# doorbell.net
KiCad netlist of a schematic drawn in EAGLE
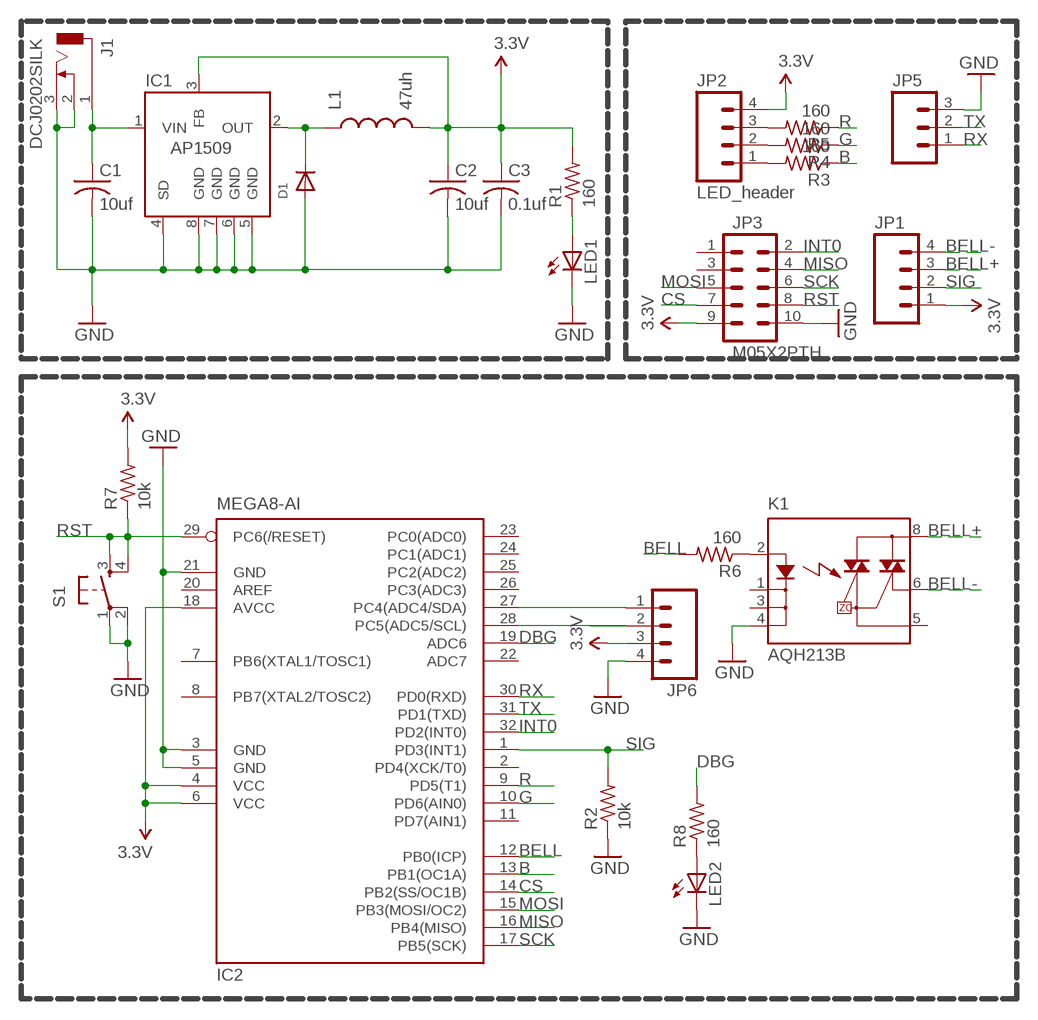
[diagram p0: schematic, sheet 1]

(export (version "E")
  (design (tool "Eeschema 10.0.6"))
  (components
    (comp (ref "C1")
      (value "10uf")
      (footprint "eagle-import:C1206")
      (libsource (lib "eagle-import") (part "C-USC1206"))
    )
    (comp (ref "C2")
      (value "10uf")
      (footprint "eagle-import:C1206")
      (libsource (lib "eagle-import") (part "C-USC1206"))
    )
    (comp (ref "C3")
      (value "0.1uf")
      (footprint "eagle-import:C1206")
      (libsource (lib "eagle-import") (part "C-USC1206"))
    )
    (comp (ref "D1")
      (value "DIODESOD-123")
      (footprint "eagle-import:SOD-123")
      (libsource (lib "eagle-import") (part "DIODESOD-123"))
    )
    (comp (ref "IC1")
      (value "AP1509")
      (footprint "eagle-import:SOP-8")
      (libsource (lib "eagle-import") (part "AP1509"))
    )
    (comp (ref "IC2")
      (value "MEGA8-AI")
      (footprint "eagle-import:TQFP32-08")
      (fields (field (name "MPN") "ATMEGA8-16AU"))
      (libsource (lib "eagle-import") (part "MEGA8-AI"))
    )
    (comp (ref "J1")
      (value "DCJ0202SILK")
      (footprint "eagle-import:DCJ0202_SILK")
      (libsource (lib "eagle-import") (part "DCJ0202SILK"))
    )
    (comp (ref "JP1")
      (value "M04SCREW_SILK")
      (footprint "eagle-import:SCREWTERMINAL-3.5MM-4_SILK")
      (libsource (lib "eagle-import") (part "M04SCREW_SILK"))
    )
    (comp (ref "JP2")
      (value "LED_header")
      (footprint "eagle-import:1X04")
      (libsource (lib "eagle-import") (part "M04PTH"))
    )
    (comp (ref "JP3")
      (value "M05X2PTH")
      (footprint "eagle-import:AVR_ICSP")
      (libsource (lib "eagle-import") (part "M05X2PTH"))
    )
    (comp (ref "JP5")
      (value "M03PTH")
      (footprint "eagle-import:1X03")
      (libsource (lib "eagle-import") (part "M03PTH"))
    )
    (comp (ref "JP6")
      (value "M04PTH")
      (footprint "eagle-import:1X04")
      (libsource (lib "eagle-import") (part "M04PTH"))
    )
    (comp (ref "K1")
      (value "AQH213B")
      (footprint "eagle-import:DIL08SMD")
      (libsource (lib "eagle-import") (part "AQH213B"))
    )
    (comp (ref "L1")
      (value "47uh")
      (footprint "eagle-import:1210")
      (libsource (lib "eagle-import") (part "INDUCTOR1210"))
    )
    (comp (ref "LED1")
      (value "LEDSMT1206")
      (footprint "eagle-import:1206")
      (libsource (lib "eagle-import") (part "LEDSMT1206"))
    )
    (comp (ref "LED2")
      (value "LEDSMT1206")
      (footprint "eagle-import:1206")
      (libsource (lib "eagle-import") (part "LEDSMT1206"))
    )
    (comp (ref "R1")
      (value "160")
      (footprint "eagle-import:R1206")
      (libsource (lib "eagle-import") (part "R-US_R1206"))
    )
    (comp (ref "R2")
      (value "10k")
      (footprint "eagle-import:R1206")
      (libsource (lib "eagle-import") (part "R-US_R1206"))
    )
    (comp (ref "R3")
      (value "160")
      (footprint "eagle-import:R1206")
      (libsource (lib "eagle-import") (part "R-US_R1206"))
    )
    (comp (ref "R4")
      (value "160")
      (footprint "eagle-import:R1206")
      (libsource (lib "eagle-import") (part "R-US_R1206"))
    )
    (comp (ref "R5")
      (value "160")
      (footprint "eagle-import:R1206")
      (libsource (lib "eagle-import") (part "R-US_R1206"))
    )
    (comp (ref "R6")
      (value "160")
      (footprint "eagle-import:R1206")
      (libsource (lib "eagle-import") (part "R-US_R1206"))
    )
    (comp (ref "R7")
      (value "10k")
      (footprint "eagle-import:R1206")
      (libsource (lib "eagle-import") (part "R-US_R1206"))
    )
    (comp (ref "R8")
      (value "160")
      (footprint "eagle-import:R1206")
      (libsource (lib "eagle-import") (part "R-US_R1206"))
    )
    (comp (ref "S1")
      (value "TAC_SWITCHSMD")
      (footprint "eagle-import:TACTILE_SWITCH_SMD")
      (libsource (lib "eagle-import") (part "TAC_SWITCHSMD"))
    )
  )
  (nets
    (net (code "1") (name "/B") (class "Default")
      (node (ref "IC2") (pin "13") (pinfunction "PB1(OC1A)_13") (pintype "bidirectional"))
      (node (ref "R3") (pin "1") (pinfunction "1_1") (pintype "passive"))
    )
    (net (code "2") (name "/BELL") (class "Default")
      (node (ref "IC2") (pin "12") (pinfunction "PB0(ICP)_12") (pintype "bidirectional"))
      (node (ref "R6") (pin "2") (pinfunction "2_2") (pintype "passive"))
    )
    (net (code "3") (name "/BELL+") (class "Default")
      (node (ref "JP1") (pin "3") (pinfunction "3_3") (pintype "passive"))
      (node (ref "K1") (pin "8") (pinfunction "DS1_8") (pintype "passive"))
    )
    (net (code "4") (name "/BELL-") (class "Default")
      (node (ref "JP1") (pin "4") (pinfunction "4_4") (pintype "passive"))
      (node (ref "K1") (pin "6") (pinfunction "DS3_6") (pintype "passive"))
    )
    (net (code "5") (name "/CS") (class "Default")
      (node (ref "IC2") (pin "14") (pinfunction "PB2(SS/OC1B)_14") (pintype "bidirectional"))
      (node (ref "JP3") (pin "7") (pinfunction "7_7") (pintype "passive"))
    )
    (net (code "6") (name "/DBG") (class "Default")
      (node (ref "IC2") (pin "19") (pinfunction "ADC6_19") (pintype "bidirectional"))
      (node (ref "R8") (pin "2") (pinfunction "2_2") (pintype "passive"))
    )
    (net (code "7") (name "/G") (class "Default")
      (node (ref "IC2") (pin "10") (pinfunction "PD6(AIN0)_10") (pintype "bidirectional"))
      (node (ref "R4") (pin "1") (pinfunction "1_1") (pintype "passive"))
    )
    (net (code "8") (name "/INT0") (class "Default")
      (node (ref "IC2") (pin "32") (pinfunction "PD2(INT0)_32") (pintype "bidirectional"))
      (node (ref "JP3") (pin "2") (pinfunction "2_2") (pintype "passive"))
    )
    (net (code "9") (name "/MISO") (class "Default")
      (node (ref "IC2") (pin "16") (pinfunction "PB4(MISO)_16") (pintype "bidirectional"))
      (node (ref "JP3") (pin "4") (pinfunction "4_4") (pintype "passive"))
    )
    (net (code "10") (name "/MOSI") (class "Default")
      (node (ref "IC2") (pin "15") (pinfunction "PB3(MOSI/OC2)_15") (pintype "bidirectional"))
      (node (ref "JP3") (pin "5") (pinfunction "5_5") (pintype "passive"))
    )
    (net (code "11") (name "/R") (class "Default")
      (node (ref "IC2") (pin "9") (pinfunction "PD5(T1)_9") (pintype "bidirectional"))
      (node (ref "R5") (pin "1") (pinfunction "1_1") (pintype "passive"))
    )
    (net (code "12") (name "/RST") (class "Default")
      (node (ref "IC2") (pin "29") (pinfunction "PC6(/RESET)_29") (pintype "bidirectional"))
      (node (ref "JP3") (pin "8") (pinfunction "8_8") (pintype "passive"))
      (node (ref "R7") (pin "1") (pinfunction "1_1") (pintype "passive"))
      (node (ref "S1") (pin "3") (pinfunction "3_3") (pintype "passive"))
      (node (ref "S1") (pin "4") (pinfunction "4_4") (pintype "passive"))
    )
    (net (code "13") (name "/RX") (class "Default")
      (node (ref "IC2") (pin "30") (pinfunction "PD0(RXD)_30") (pintype "bidirectional"))
      (node (ref "JP5") (pin "1") (pinfunction "1_1") (pintype "passive"))
    )
    (net (code "14") (name "/SCK") (class "Default")
      (node (ref "IC2") (pin "17") (pinfunction "PB5(SCK)_17") (pintype "bidirectional"))
      (node (ref "JP3") (pin "6") (pinfunction "6_6") (pintype "passive"))
    )
    (net (code "15") (name "/SIG") (class "Default")
      (node (ref "IC2") (pin "1") (pinfunction "PD3(INT1)_1") (pintype "bidirectional"))
      (node (ref "JP1") (pin "2") (pinfunction "2_2") (pintype "passive"))
      (node (ref "R2") (pin "2") (pinfunction "2_2") (pintype "passive"))
    )
    (net (code "16") (name "/TX") (class "Default")
      (node (ref "IC2") (pin "31") (pinfunction "PD1(TXD)_31") (pintype "bidirectional"))
      (node (ref "JP5") (pin "2") (pinfunction "2_2") (pintype "passive"))
    )
    (net (code "17") (name "3.3V") (class "Default")
      (node (ref "C2") (pin "1") (pinfunction "1_1") (pintype "passive"))
      (node (ref "C3") (pin "1") (pinfunction "1_1") (pintype "passive"))
      (node (ref "IC1") (pin "3") (pinfunction "FB_3") (pintype "bidirectional"))
      (node (ref "IC2") (pin "18") (pinfunction "AVCC_18") (pintype "power_in"))
      (node (ref "IC2") (pin "4") (pinfunction "VCC_4") (pintype "power_in"))
      (node (ref "IC2") (pin "6") (pinfunction "VCC_6") (pintype "power_in"))
      (node (ref "JP1") (pin "1") (pinfunction "1_1") (pintype "passive"))
      (node (ref "JP2") (pin "4") (pinfunction "4_4") (pintype "passive"))
      (node (ref "JP3") (pin "9") (pinfunction "9_9") (pintype "passive"))
      (node (ref "JP6") (pin "3") (pinfunction "3_3") (pintype "passive"))
      (node (ref "L1") (pin "2") (pinfunction "2_2") (pintype "passive"))
      (node (ref "R1") (pin "2") (pinfunction "2_2") (pintype "passive"))
      (node (ref "R7") (pin "2") (pinfunction "2_2") (pintype "passive"))
    )
    (net (code "18") (name "GND") (class "Default")
      (node (ref "C1") (pin "2") (pinfunction "2_2") (pintype "passive"))
      (node (ref "C2") (pin "2") (pinfunction "2_2") (pintype "passive"))
      (node (ref "C3") (pin "2") (pinfunction "2_2") (pintype "passive"))
      (node (ref "D1") (pin "A") (pinfunction "A_A") (pintype "passive"))
      (node (ref "IC1") (pin "4") (pinfunction "SD_4") (pintype "bidirectional"))
      (node (ref "IC1") (pin "5") (pinfunction "GND_5") (pintype "bidirectional"))
      (node (ref "IC1") (pin "6") (pinfunction "GND_6") (pintype "bidirectional"))
      (node (ref "IC1") (pin "7") (pinfunction "GND_7") (pintype "bidirectional"))
      (node (ref "IC1") (pin "8") (pinfunction "GND_8") (pintype "bidirectional"))
      (node (ref "IC2") (pin "21") (pinfunction "GND_21") (pintype "power_in"))
      (node (ref "IC2") (pin "3") (pinfunction "GND_3") (pintype "power_in"))
      (node (ref "IC2") (pin "5") (pinfunction "GND_5") (pintype "power_in"))
      (node (ref "J1") (pin "2") (pinfunction "2_2") (pintype "passive"))
      (node (ref "J1") (pin "3") (pinfunction "3_3") (pintype "passive"))
      (node (ref "JP3") (pin "10") (pinfunction "10_10") (pintype "passive"))
      (node (ref "JP5") (pin "3") (pinfunction "3_3") (pintype "passive"))
      (node (ref "JP6") (pin "4") (pinfunction "4_4") (pintype "passive"))
      (node (ref "K1") (pin "4") (pinfunction "K2_4") (pintype "passive"))
      (node (ref "LED1") (pin "C") (pinfunction "C_C") (pintype "passive"))
      (node (ref "LED2") (pin "C") (pinfunction "C_C") (pintype "passive"))
      (node (ref "R2") (pin "1") (pinfunction "1_1") (pintype "passive"))
      (node (ref "S1") (pin "1") (pinfunction "1_1") (pintype "passive"))
      (node (ref "S1") (pin "2") (pinfunction "2_2") (pintype "passive"))
    )
    (net (code "19") (name "Net-(IC1-OUT)") (class "Default")
      (node (ref "D1") (pin "C") (pinfunction "C_C") (pintype "passive"))
      (node (ref "IC1") (pin "2") (pinfunction "OUT_2") (pintype "bidirectional"))
      (node (ref "L1") (pin "1") (pinfunction "1_1") (pintype "passive"))
    )
    (net (code "20") (name "Net-(IC1-VIN)") (class "Default")
      (node (ref "C1") (pin "1") (pinfunction "1_1") (pintype "passive"))
      (node (ref "IC1") (pin "1") (pinfunction "VIN_1") (pintype "bidirectional"))
      (node (ref "J1") (pin "1") (pinfunction "1_1") (pintype "passive"))
    )
    (net (code "21") (name "Net-(IC2-PC4(ADC4{slash}SDA))") (class "Default")
      (node (ref "IC2") (pin "27") (pinfunction "PC4(ADC4/SDA)_27") (pintype "bidirectional"))
      (node (ref "JP6") (pin "1") (pinfunction "1_1") (pintype "passive"))
    )
    (net (code "22") (name "Net-(IC2-PC5(ADC5{slash}SCL))") (class "Default")
      (node (ref "IC2") (pin "28") (pinfunction "PC5(ADC5/SCL)_28") (pintype "bidirectional"))
      (node (ref "JP6") (pin "2") (pinfunction "2_2") (pintype "passive"))
    )
    (net (code "23") (name "Net-(JP2-Pad1)") (class "Default")
      (node (ref "JP2") (pin "1") (pinfunction "1_1") (pintype "passive"))
      (node (ref "R3") (pin "2") (pinfunction "2_2") (pintype "passive"))
    )
    (net (code "24") (name "Net-(JP2-Pad2)") (class "Default")
      (node (ref "JP2") (pin "2") (pinfunction "2_2") (pintype "passive"))
      (node (ref "R4") (pin "2") (pinfunction "2_2") (pintype "passive"))
    )
    (net (code "25") (name "Net-(JP2-Pad3)") (class "Default")
      (node (ref "JP2") (pin "3") (pinfunction "3_3") (pintype "passive"))
      (node (ref "R5") (pin "2") (pinfunction "2_2") (pintype "passive"))
    )
    (net (code "26") (name "Net-(K1-A)") (class "Default")
      (node (ref "K1") (pin "2") (pinfunction "A_2") (pintype "passive"))
      (node (ref "R6") (pin "1") (pinfunction "1_1") (pintype "passive"))
    )
    (net (code "27") (name "Net-(LED1-PadA)") (class "Default")
      (node (ref "LED1") (pin "A") (pinfunction "A_A") (pintype "passive"))
      (node (ref "R1") (pin "1") (pinfunction "1_1") (pintype "passive"))
    )
    (net (code "28") (name "Net-(LED2-PadA)") (class "Default")
      (node (ref "LED2") (pin "A") (pinfunction "A_A") (pintype "passive"))
      (node (ref "R8") (pin "1") (pinfunction "1_1") (pintype "passive"))
    )
    (net (code "29") (name "unconnected-(IC2-ADC7-Pad22)") (class "Default")
      (node (ref "IC2") (pin "22") (pinfunction "ADC7_22") (pintype "bidirectional"))
    )
    (net (code "30") (name "unconnected-(IC2-AREF-Pad20)") (class "Default")
      (node (ref "IC2") (pin "20") (pinfunction "AREF_20") (pintype "passive"))
    )
    (net (code "31") (name "unconnected-(IC2-PB6(XTAL1{slash}TOSC1)-Pad7)") (class "Default")
      (node (ref "IC2") (pin "7") (pinfunction "PB6(XTAL1/TOSC1)_7") (pintype "bidirectional"))
    )
    (net (code "32") (name "unconnected-(IC2-PB7(XTAL2{slash}TOSC2)-Pad8)") (class "Default")
      (node (ref "IC2") (pin "8") (pinfunction "PB7(XTAL2/TOSC2)_8") (pintype "bidirectional"))
    )
    (net (code "33") (name "unconnected-(IC2-PC0(ADC0)-Pad23)") (class "Default")
      (node (ref "IC2") (pin "23") (pinfunction "PC0(ADC0)_23") (pintype "bidirectional"))
    )
    (net (code "34") (name "unconnected-(IC2-PC1(ADC1)-Pad24)") (class "Default")
      (node (ref "IC2") (pin "24") (pinfunction "PC1(ADC1)_24") (pintype "bidirectional"))
    )
    (net (code "35") (name "unconnected-(IC2-PC2(ADC2)-Pad25)") (class "Default")
      (node (ref "IC2") (pin "25") (pinfunction "PC2(ADC2)_25") (pintype "bidirectional"))
    )
    (net (code "36") (name "unconnected-(IC2-PC3(ADC3)-Pad26)") (class "Default")
      (node (ref "IC2") (pin "26") (pinfunction "PC3(ADC3)_26") (pintype "bidirectional"))
    )
    (net (code "37") (name "unconnected-(IC2-PD4(XCK{slash}T0)-Pad2)") (class "Default")
      (node (ref "IC2") (pin "2") (pinfunction "PD4(XCK/T0)_2") (pintype "bidirectional"))
    )
    (net (code "38") (name "unconnected-(IC2-PD7(AIN1)-Pad11)") (class "Default")
      (node (ref "IC2") (pin "11") (pinfunction "PD7(AIN1)_11") (pintype "bidirectional"))
    )
    (net (code "39") (name "unconnected-(JP3-Pad1)") (class "Default")
      (node (ref "JP3") (pin "1") (pinfunction "1_1") (pintype "passive"))
    )
    (net (code "40") (name "unconnected-(JP3-Pad3)") (class "Default")
      (node (ref "JP3") (pin "3") (pinfunction "3_3") (pintype "passive"))
    )
    (net (code "41") (name "unconnected-(K1-DS2-Pad5)") (class "Default")
      (node (ref "K1") (pin "5") (pinfunction "DS2_5") (pintype "passive"))
    )
    (net (code "42") (name "unconnected-(K1-K-Pad1)") (class "Default")
      (node (ref "K1") (pin "1") (pinfunction "K_1") (pintype "passive"))
    )
    (net (code "43") (name "unconnected-(K1-K1-Pad3)") (class "Default")
      (node (ref "K1") (pin "3") (pinfunction "K1_3") (pintype "passive"))
    )
  )
)
